# mbavr-1t.net
KiCad netlist of a schematic drawn in EAGLE
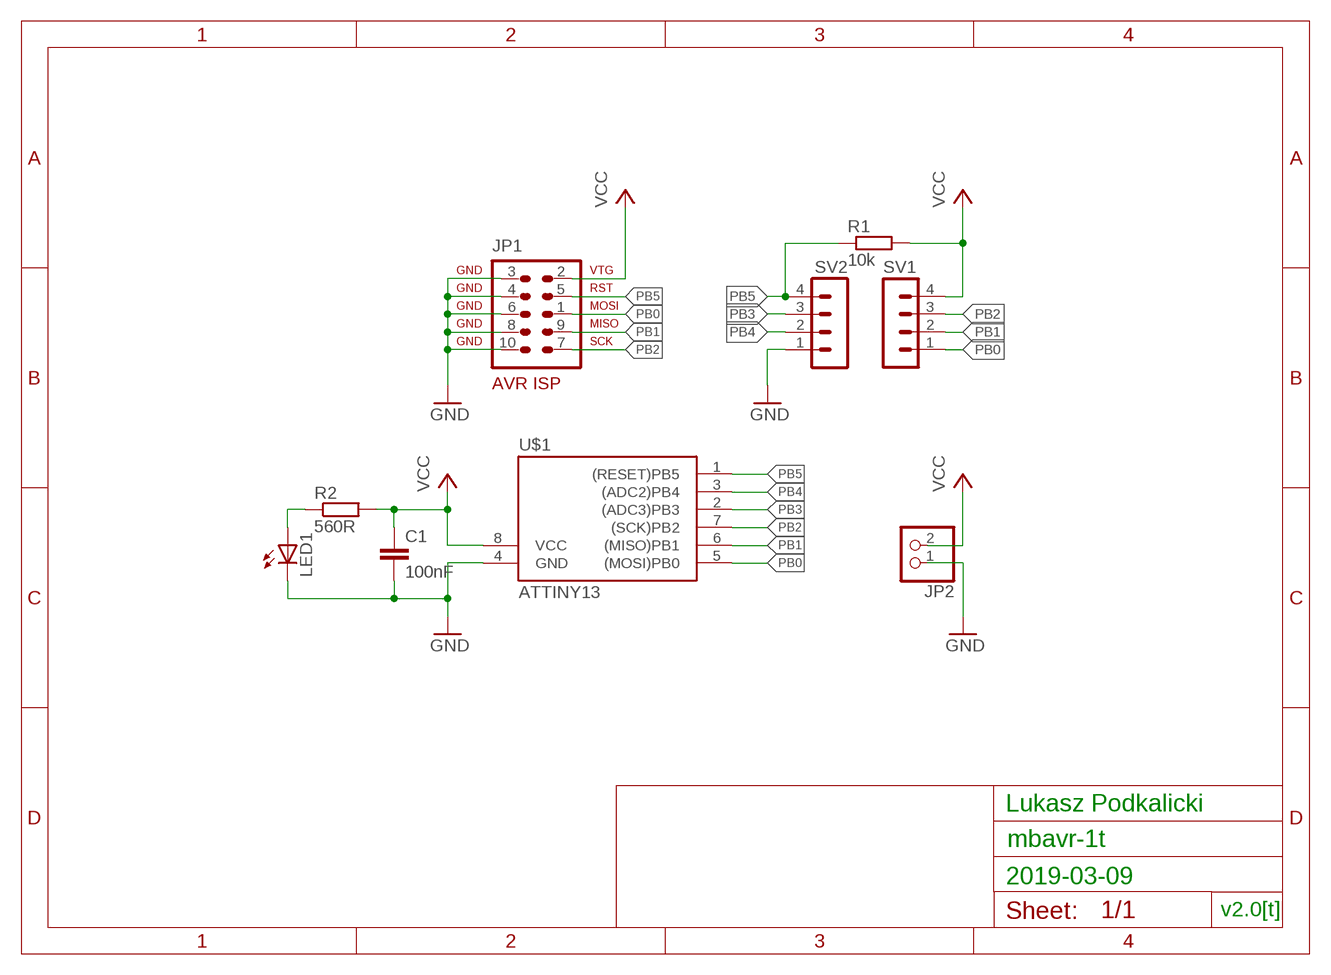
[diagram p0: schematic, sheet 1]

(export (version "E")
  (design (tool "Eeschema 10.0.6"))
  (components
    (comp (ref "C1")
      (value "100nF")
      (footprint "eagle-import:C1206K")
      (libsource (lib "eagle-import") (part "C-EUC1206K"))
    )
    (comp (ref "JP1")
      (value "AVR-ISP-10")
      (footprint "eagle-import:AVR-ISP-10")
      (libsource (lib "eagle-import") (part "AVR-ISP-10"))
    )
    (comp (ref "JP2")
      (value "PINHD-1X2")
      (footprint "eagle-import:1X02")
      (libsource (lib "eagle-import") (part "PINHD-1X2"))
    )
    (comp (ref "LED1")
      (value "LEDSML1206")
      (footprint "eagle-import:SML1206")
      (libsource (lib "eagle-import") (part "LEDSML1206"))
    )
    (comp (ref "R1")
      (value "10k")
      (footprint "eagle-import:R1206")
      (libsource (lib "eagle-import") (part "R-EU_R1206"))
    )
    (comp (ref "R2")
      (value "560R")
      (footprint "eagle-import:R1206")
      (libsource (lib "eagle-import") (part "R-EU_R1206"))
    )
    (comp (ref "SV1")
      (value "MA04-1")
      (footprint "eagle-import:MA04-1")
      (libsource (lib "eagle-import") (part "MA04-1"))
    )
    (comp (ref "SV2")
      (value "MA04-1")
      (footprint "eagle-import:MA04-1")
      (libsource (lib "eagle-import") (part "MA04-1"))
    )
    (comp (ref "U$1")
      (value "ATTINY13")
      (footprint "eagle-import:DIL08")
      (libsource (lib "eagle-import") (part "TINY138P3"))
    )
  )
  (nets
    (net (code "1") (name "GND") (class "Default")
      (node (ref "C1") (pin "2") (pinfunction "2_2") (pintype "passive"))
      (node (ref "JP1") (pin "10") (pinfunction "10_10") (pintype "passive"))
      (node (ref "JP1") (pin "3") (pinfunction "3_3") (pintype "passive"))
      (node (ref "JP1") (pin "4") (pinfunction "4_4") (pintype "passive"))
      (node (ref "JP1") (pin "6") (pinfunction "6_6") (pintype "passive"))
      (node (ref "JP1") (pin "8") (pinfunction "8_8") (pintype "passive"))
      (node (ref "JP2") (pin "1") (pinfunction "1_1") (pintype "passive"))
      (node (ref "LED1") (pin "C") (pinfunction "C_C") (pintype "passive"))
      (node (ref "SV2") (pin "1") (pinfunction "1_1") (pintype "passive"))
      (node (ref "U$1") (pin "4") (pinfunction "GND_4") (pintype "power_in"))
    )
    (net (code "2") (name "Net-(LED1-PadA)") (class "Default")
      (node (ref "LED1") (pin "A") (pinfunction "A_A") (pintype "passive"))
      (node (ref "R2") (pin "1") (pinfunction "1_1") (pintype "passive"))
    )
    (net (code "3") (name "PB0") (class "Default")
      (node (ref "JP1") (pin "1") (pinfunction "1_1") (pintype "passive"))
      (node (ref "SV1") (pin "1") (pinfunction "1_1") (pintype "passive"))
      (node (ref "U$1") (pin "5") (pinfunction "(MOSI)PB0_5") (pintype "bidirectional"))
    )
    (net (code "4") (name "PB1") (class "Default")
      (node (ref "JP1") (pin "9") (pinfunction "9_9") (pintype "passive"))
      (node (ref "SV1") (pin "2") (pinfunction "2_2") (pintype "passive"))
      (node (ref "U$1") (pin "6") (pinfunction "(MISO)PB1_6") (pintype "bidirectional"))
    )
    (net (code "5") (name "PB2") (class "Default")
      (node (ref "JP1") (pin "7") (pinfunction "7_7") (pintype "passive"))
      (node (ref "SV1") (pin "3") (pinfunction "3_3") (pintype "passive"))
      (node (ref "U$1") (pin "7") (pinfunction "(SCK)PB2_7") (pintype "bidirectional"))
    )
    (net (code "6") (name "PB3") (class "Default")
      (node (ref "SV2") (pin "3") (pinfunction "3_3") (pintype "passive"))
      (node (ref "U$1") (pin "2") (pinfunction "(ADC3)PB3_2") (pintype "bidirectional"))
    )
    (net (code "7") (name "PB4") (class "Default")
      (node (ref "SV2") (pin "2") (pinfunction "2_2") (pintype "passive"))
      (node (ref "U$1") (pin "3") (pinfunction "(ADC2)PB4_3") (pintype "bidirectional"))
    )
    (net (code "8") (name "PB5") (class "Default")
      (node (ref "JP1") (pin "5") (pinfunction "5_5") (pintype "passive"))
      (node (ref "R1") (pin "1") (pinfunction "1_1") (pintype "passive"))
      (node (ref "SV2") (pin "4") (pinfunction "4_4") (pintype "passive"))
      (node (ref "U$1") (pin "1") (pinfunction "(RESET)PB5_1") (pintype "bidirectional"))
    )
    (net (code "9") (name "VCC") (class "Default")
      (node (ref "C1") (pin "1") (pinfunction "1_1") (pintype "passive"))
      (node (ref "JP1") (pin "2") (pinfunction "2_2") (pintype "passive"))
      (node (ref "JP2") (pin "2") (pinfunction "2_2") (pintype "passive"))
      (node (ref "R1") (pin "2") (pinfunction "2_2") (pintype "passive"))
      (node (ref "R2") (pin "2") (pinfunction "2_2") (pintype "passive"))
      (node (ref "SV1") (pin "4") (pinfunction "4_4") (pintype "passive"))
      (node (ref "U$1") (pin "8") (pinfunction "VCC_8") (pintype "power_in"))
    )
  )
)
